# FPGA_POWER.net
KiCad netlist of a schematic drawn in Altium Designer
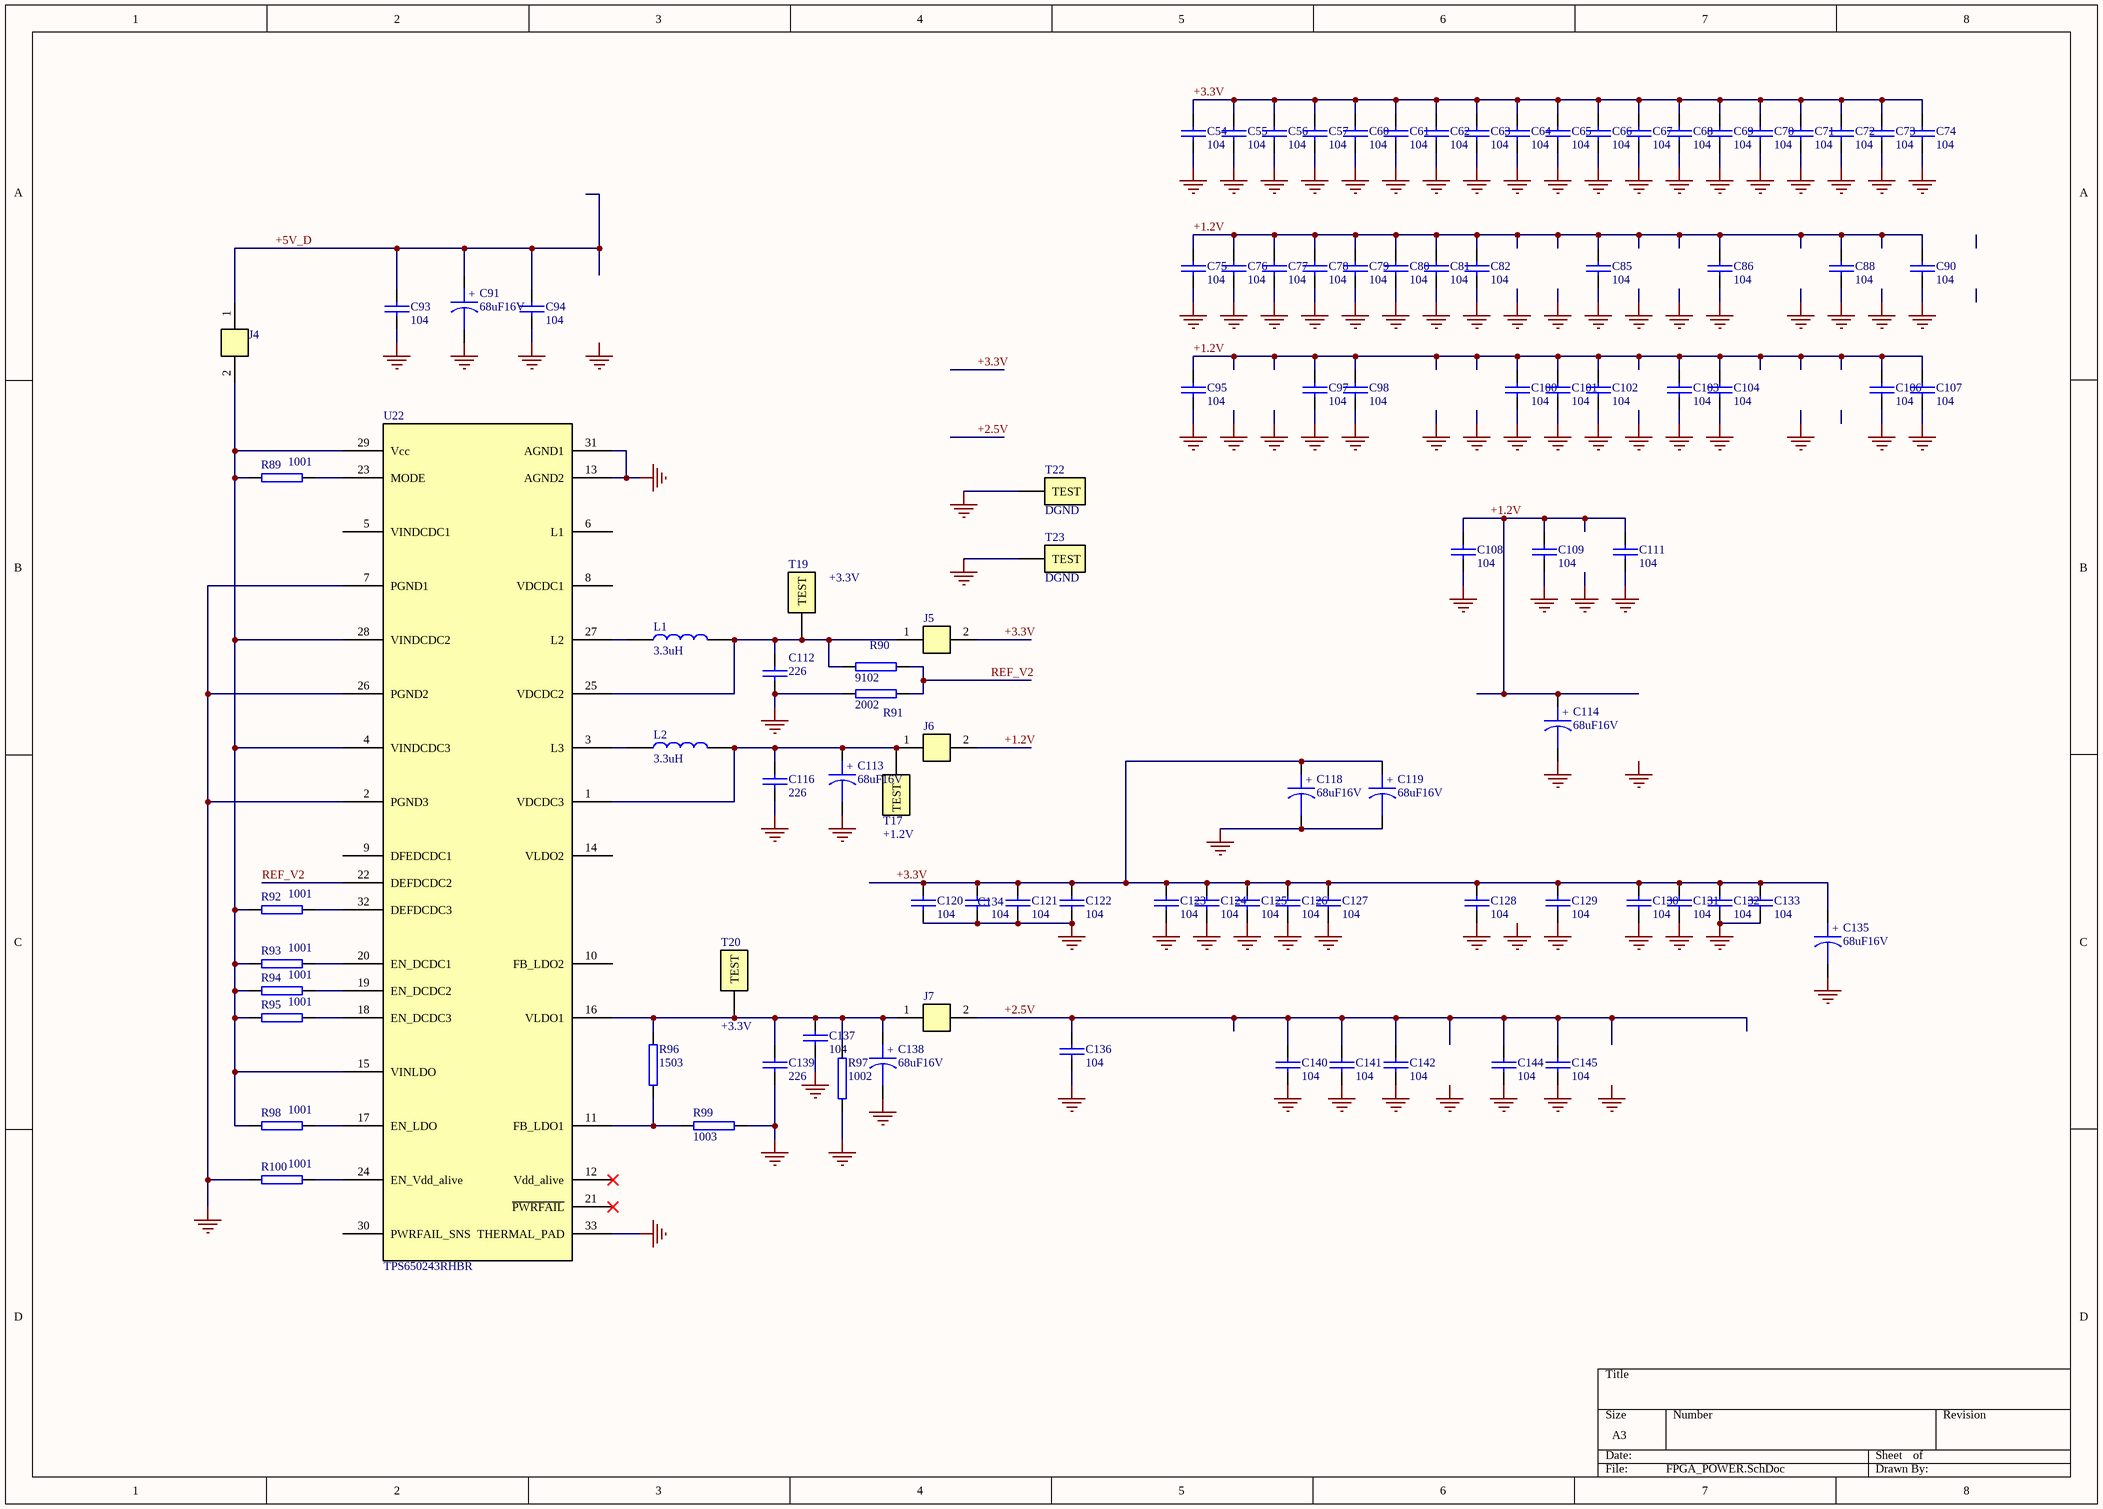
[diagram p0: FPGA_POWER.SchDoc]

(export (version "E")
  (design (tool "Eeschema 10.0.6"))
  (components
    (comp (ref "C54")
      (value "104")
      (footprint "0805C")
      (description "Capacitor")
      (libsource (lib "*") (part "CAP"))
    )
    (comp (ref "C55")
      (value "104")
      (footprint "0402C")
      (description "Capacitor")
      (libsource (lib "*") (part "CAP"))
    )
    (comp (ref "C56")
      (value "104")
      (footprint "0402C")
      (description "Capacitor")
      (libsource (lib "*") (part "CAP"))
    )
    (comp (ref "C57")
      (value "104")
      (footprint "0402C")
      (description "Capacitor")
      (libsource (lib "*") (part "CAP"))
    )
    (comp (ref "C60")
      (value "104")
      (footprint "0402C")
      (description "Capacitor")
      (libsource (lib "*") (part "CAP"))
    )
    (comp (ref "C61")
      (value "104")
      (footprint "0402C")
      (description "Capacitor")
      (libsource (lib "*") (part "CAP"))
    )
    (comp (ref "C62")
      (value "104")
      (footprint "0402C")
      (description "Capacitor")
      (libsource (lib "*") (part "CAP"))
    )
    (comp (ref "C63")
      (value "104")
      (footprint "0402C")
      (description "Capacitor")
      (libsource (lib "*") (part "CAP"))
    )
    (comp (ref "C64")
      (value "104")
      (footprint "0402C")
      (description "Capacitor")
      (libsource (lib "*") (part "CAP"))
    )
    (comp (ref "C65")
      (value "104")
      (footprint "0402C")
      (description "Capacitor")
      (libsource (lib "*") (part "CAP"))
    )
    (comp (ref "C66")
      (value "104")
      (footprint "0402C")
      (description "Capacitor")
      (libsource (lib "*") (part "CAP"))
    )
    (comp (ref "C67")
      (value "104")
      (footprint "0402C")
      (description "Capacitor")
      (libsource (lib "*") (part "CAP"))
    )
    (comp (ref "C68")
      (value "104")
      (footprint "0402C")
      (description "Capacitor")
      (libsource (lib "*") (part "CAP"))
    )
    (comp (ref "C69")
      (value "104")
      (footprint "0402C")
      (description "Capacitor")
      (libsource (lib "*") (part "CAP"))
    )
    (comp (ref "C70")
      (value "104")
      (footprint "0402C")
      (description "Capacitor")
      (libsource (lib "*") (part "CAP"))
    )
    (comp (ref "C71")
      (value "104")
      (footprint "0402C")
      (description "Capacitor")
      (libsource (lib "*") (part "CAP"))
    )
    (comp (ref "C72")
      (value "104")
      (footprint "0402C")
      (description "Capacitor")
      (libsource (lib "*") (part "CAP"))
    )
    (comp (ref "C73")
      (value "104")
      (footprint "0402C")
      (description "Capacitor")
      (libsource (lib "*") (part "CAP"))
    )
    (comp (ref "C74")
      (value "104")
      (footprint "0402C")
      (description "Capacitor")
      (libsource (lib "*") (part "CAP"))
    )
    (comp (ref "C75")
      (value "104")
      (footprint "0805C")
      (description "Capacitor")
      (libsource (lib "*") (part "CAP"))
    )
    (comp (ref "C76")
      (value "104")
      (footprint "0402C")
      (description "Capacitor")
      (libsource (lib "*") (part "CAP"))
    )
    (comp (ref "C77")
      (value "104")
      (footprint "0402C")
      (description "Capacitor")
      (libsource (lib "*") (part "CAP"))
    )
    (comp (ref "C78")
      (value "104")
      (footprint "0805C")
      (description "Capacitor")
      (libsource (lib "*") (part "CAP"))
    )
    (comp (ref "C79")
      (value "104")
      (footprint "0402C")
      (description "Capacitor")
      (libsource (lib "*") (part "CAP"))
    )
    (comp (ref "C80")
      (value "104")
      (footprint "0402C")
      (description "Capacitor")
      (libsource (lib "*") (part "CAP"))
    )
    (comp (ref "C81")
      (value "104")
      (footprint "0402C")
      (description "Capacitor")
      (libsource (lib "*") (part "CAP"))
    )
    (comp (ref "C82")
      (value "104")
      (footprint "0402C")
      (description "Capacitor")
      (libsource (lib "*") (part "CAP"))
    )
    (comp (ref "C85")
      (value "104")
      (footprint "0402C")
      (description "Capacitor")
      (libsource (lib "*") (part "CAP"))
    )
    (comp (ref "C86")
      (value "104")
      (footprint "0402C")
      (description "Capacitor")
      (libsource (lib "*") (part "CAP"))
    )
    (comp (ref "C88")
      (value "104")
      (footprint "0402C")
      (description "Capacitor")
      (libsource (lib "*") (part "CAP"))
    )
    (comp (ref "C90")
      (value "104")
      (footprint "0402C")
      (description "Capacitor")
      (libsource (lib "*") (part "CAP"))
    )
    (comp (ref "C91")
      (value "68uF16V")
      (footprint "6032")
      (description "Capacitor")
      (libsource (lib "*") (part "CAPACITOR POL"))
    )
    (comp (ref "C93")
      (value "104")
      (footprint "0805C")
      (description "Capacitor")
      (libsource (lib "*") (part "CAP"))
    )
    (comp (ref "C94")
      (value "104")
      (footprint "0805C")
      (description "Capacitor")
      (libsource (lib "*") (part "CAP"))
    )
    (comp (ref "C95")
      (value "104")
      (footprint "0402C")
      (description "Capacitor")
      (libsource (lib "*") (part "CAP"))
    )
    (comp (ref "C97")
      (value "104")
      (footprint "0402C")
      (description "Capacitor")
      (libsource (lib "*") (part "CAP"))
    )
    (comp (ref "C98")
      (value "104")
      (footprint "0402C")
      (description "Capacitor")
      (libsource (lib "*") (part "CAP"))
    )
    (comp (ref "C100")
      (value "104")
      (footprint "0402C")
      (description "Capacitor")
      (libsource (lib "*") (part "CAP"))
    )
    (comp (ref "C101")
      (value "104")
      (footprint "0402C")
      (description "Capacitor")
      (libsource (lib "*") (part "CAP"))
    )
    (comp (ref "C102")
      (value "104")
      (footprint "0402C")
      (description "Capacitor")
      (libsource (lib "*") (part "CAP"))
    )
    (comp (ref "C103")
      (value "104")
      (footprint "0402C")
      (description "Capacitor")
      (libsource (lib "*") (part "CAP"))
    )
    (comp (ref "C104")
      (value "104")
      (footprint "0402C")
      (description "Capacitor")
      (libsource (lib "*") (part "CAP"))
    )
    (comp (ref "C106")
      (value "104")
      (footprint "0402C")
      (description "Capacitor")
      (libsource (lib "*") (part "CAP"))
    )
    (comp (ref "C107")
      (value "104")
      (footprint "0402C")
      (description "Capacitor")
      (libsource (lib "*") (part "CAP"))
    )
    (comp (ref "C108")
      (value "104")
      (footprint "0402C")
      (description "Capacitor")
      (libsource (lib "*") (part "CAP"))
    )
    (comp (ref "C109")
      (value "104")
      (footprint "0402C")
      (description "Capacitor")
      (libsource (lib "*") (part "CAP"))
    )
    (comp (ref "C111")
      (value "104")
      (footprint "0402C")
      (description "Capacitor")
      (libsource (lib "*") (part "CAP"))
    )
    (comp (ref "C112")
      (value "226")
      (footprint "C226")
      (description "Capacitor")
      (libsource (lib "*") (part "CAP"))
    )
    (comp (ref "C113")
      (value "68uF16V")
      (footprint "6032")
      (description "Capacitor")
      (libsource (lib "*") (part "CAPACITOR POL"))
    )
    (comp (ref "C114")
      (value "68uF16V")
      (footprint "6032")
      (description "Capacitor")
      (libsource (lib "*") (part "CAPACITOR POL"))
    )
    (comp (ref "C116")
      (value "226")
      (footprint "C226")
      (description "Capacitor")
      (libsource (lib "*") (part "CAP"))
    )
    (comp (ref "C118")
      (value "68uF16V")
      (footprint "6032")
      (description "Capacitor")
      (libsource (lib "*") (part "CAPACITOR POL"))
    )
    (comp (ref "C119")
      (value "68uF16V")
      (footprint "6032")
      (description "Capacitor")
      (libsource (lib "*") (part "CAPACITOR POL"))
    )
    (comp (ref "C120")
      (value "104")
      (footprint "0402C")
      (description "Capacitor")
      (libsource (lib "*") (part "CAP"))
    )
    (comp (ref "C121")
      (value "104")
      (footprint "0402C")
      (description "Capacitor")
      (libsource (lib "*") (part "CAP"))
    )
    (comp (ref "C122")
      (value "104")
      (footprint "0805C")
      (description "Capacitor")
      (libsource (lib "*") (part "CAP"))
    )
    (comp (ref "C123")
      (value "104")
      (footprint "0805C")
      (description "Capacitor")
      (libsource (lib "*") (part "CAP"))
    )
    (comp (ref "C124")
      (value "104")
      (footprint "0805C")
      (description "Capacitor")
      (libsource (lib "*") (part "CAP"))
    )
    (comp (ref "C125")
      (value "104")
      (footprint "0805C")
      (description "Capacitor")
      (libsource (lib "*") (part "CAP"))
    )
    (comp (ref "C126")
      (value "104")
      (footprint "0805C")
      (description "Capacitor")
      (libsource (lib "*") (part "CAP"))
    )
    (comp (ref "C127")
      (value "104")
      (footprint "0402C")
      (description "Capacitor")
      (libsource (lib "*") (part "CAP"))
    )
    (comp (ref "C128")
      (value "104")
      (footprint "0805C")
      (description "Capacitor")
      (libsource (lib "*") (part "CAP"))
    )
    (comp (ref "C129")
      (value "104")
      (footprint "0402C")
      (description "Capacitor")
      (libsource (lib "*") (part "CAP"))
    )
    (comp (ref "C130")
      (value "104")
      (footprint "0402C")
      (description "Capacitor")
      (libsource (lib "*") (part "CAP"))
    )
    (comp (ref "C131")
      (value "104")
      (footprint "0402C")
      (description "Capacitor")
      (libsource (lib "*") (part "CAP"))
    )
    (comp (ref "C132")
      (value "104")
      (footprint "0402C")
      (description "Capacitor")
      (libsource (lib "*") (part "CAP"))
    )
    (comp (ref "C133")
      (value "104")
      (footprint "0402C")
      (description "Capacitor")
      (libsource (lib "*") (part "CAP"))
    )
    (comp (ref "C134")
      (value "104")
      (footprint "0402C")
      (description "Capacitor")
      (libsource (lib "*") (part "CAP"))
    )
    (comp (ref "C135")
      (value "68uF16V")
      (footprint "6032")
      (description "Capacitor")
      (libsource (lib "*") (part "CAPACITOR POL"))
    )
    (comp (ref "C136")
      (value "104")
      (footprint "0805C")
      (description "Capacitor")
      (libsource (lib "*") (part "CAP"))
    )
    (comp (ref "C137")
      (value "104")
      (footprint "0805C")
      (description "Capacitor")
      (libsource (lib "*") (part "CAP"))
    )
    (comp (ref "C138")
      (value "68uF16V")
      (footprint "6032")
      (description "Capacitor")
      (libsource (lib "*") (part "CAPACITOR POL"))
    )
    (comp (ref "C139")
      (value "226")
      (footprint "C226")
      (description "Capacitor")
      (libsource (lib "*") (part "CAP"))
    )
    (comp (ref "C140")
      (value "104")
      (footprint "0402C")
      (description "Capacitor")
      (libsource (lib "*") (part "CAP"))
    )
    (comp (ref "C141")
      (value "104")
      (footprint "0402C")
      (description "Capacitor")
      (libsource (lib "*") (part "CAP"))
    )
    (comp (ref "C142")
      (value "104")
      (footprint "0402C")
      (description "Capacitor")
      (libsource (lib "*") (part "CAP"))
    )
    (comp (ref "C144")
      (value "104")
      (footprint "0805C")
      (description "Capacitor")
      (libsource (lib "*") (part "CAP"))
    )
    (comp (ref "C145")
      (value "104")
      (footprint "0402C")
      (description "Capacitor")
      (libsource (lib "*") (part "CAP"))
    )
    (comp (ref "J4") (value "~") (footprint "I_ON1") (libsource (lib "") (part "I_ON_1")))
    (comp (ref "J5") (value "~") (footprint "I_ON1") (libsource (lib "*") (part "I_ON")))
    (comp (ref "J6") (value "~") (footprint "I_ON1") (libsource (lib "*") (part "I_ON")))
    (comp (ref "J7") (value "~") (footprint "I_ON1") (libsource (lib "*") (part "I_ON")))
    (comp (ref "L1") (value "3.3uH") (footprint "L3R3") (libsource (lib "*") (part "L")))
    (comp (ref "L2") (value "3.3uH") (footprint "L3R3") (libsource (lib "*") (part "L")))
    (comp (ref "R89") (value "1001") (footprint "0603") (libsource (lib "*") (part "RES2")))
    (comp (ref "R90") (value "9102") (footprint "0603") (libsource (lib "*") (part "RES2")))
    (comp (ref "R91") (value "2002") (footprint "0603") (libsource (lib "*") (part "RES2")))
    (comp (ref "R92") (value "1001") (footprint "0603") (libsource (lib "*") (part "RES2")))
    (comp (ref "R93") (value "1001") (footprint "0603") (libsource (lib "*") (part "RES2")))
    (comp (ref "R94") (value "1001") (footprint "0603") (libsource (lib "*") (part "RES2")))
    (comp (ref "R95") (value "1001") (footprint "0603") (libsource (lib "*") (part "RES2")))
    (comp (ref "R96") (value "1503") (footprint "0603") (libsource (lib "*") (part "RES2")))
    (comp (ref "R97") (value "1002") (footprint "0603") (libsource (lib "") (part "RES2_1")))
    (comp (ref "R98") (value "1001") (footprint "0603") (libsource (lib "*") (part "RES2")))
    (comp (ref "R99") (value "1003") (footprint "0603") (libsource (lib "*") (part "RES2")))
    (comp (ref "R100") (value "1001") (footprint "0603") (libsource (lib "*") (part "RES2")))
    (comp (ref "T17") (value "+1.2V") (footprint "TEST") (libsource (lib "") (part "TEST_1")))
    (comp (ref "T19") (value "+3.3V") (footprint "TEST") (libsource (lib "USB30_Project") (part "TEST")))
    (comp (ref "T20") (value "+3.3V") (footprint "TEST") (libsource (lib "USB30_Project") (part "TEST")))
    (comp (ref "T22") (value "DGND") (footprint "TEST") (libsource (lib "") (part "TEST_2")))
    (comp (ref "T23") (value "DGND") (footprint "TEST") (libsource (lib "") (part "TEST_2")))
    (comp (ref "U22") (value "TPS650243RHBR") (footprint "VQFN32-1") (libsource (lib "*") (part "TPS650243")))
  )
  (nets
    (net (code "1") (name "/+1.2V") (class "Default")
      (node (ref "C100") (pin "2") (pinfunction "2_2") (pintype "passive"))
      (node (ref "C101") (pin "2") (pinfunction "2_2") (pintype "passive"))
      (node (ref "C102") (pin "2") (pinfunction "2_2") (pintype "passive"))
      (node (ref "C103") (pin "2") (pinfunction "2_2") (pintype "passive"))
      (node (ref "C104") (pin "2") (pinfunction "2_2") (pintype "passive"))
      (node (ref "C106") (pin "2") (pinfunction "2_2") (pintype "passive"))
      (node (ref "C107") (pin "2") (pinfunction "2_2") (pintype "passive"))
      (node (ref "C108") (pin "2") (pinfunction "2_2") (pintype "passive"))
      (node (ref "C109") (pin "2") (pinfunction "2_2") (pintype "passive"))
      (node (ref "C111") (pin "2") (pinfunction "2_2") (pintype "passive"))
      (node (ref "C114") (pin "1") (pinfunction "1_1") (pintype "passive"))
      (node (ref "C75") (pin "2") (pinfunction "2_2") (pintype "passive"))
      (node (ref "C76") (pin "2") (pinfunction "2_2") (pintype "passive"))
      (node (ref "C77") (pin "2") (pinfunction "2_2") (pintype "passive"))
      (node (ref "C78") (pin "2") (pinfunction "2_2") (pintype "passive"))
      (node (ref "C79") (pin "2") (pinfunction "2_2") (pintype "passive"))
      (node (ref "C80") (pin "2") (pinfunction "2_2") (pintype "passive"))
      (node (ref "C81") (pin "2") (pinfunction "2_2") (pintype "passive"))
      (node (ref "C82") (pin "2") (pinfunction "2_2") (pintype "passive"))
      (node (ref "C85") (pin "2") (pinfunction "2_2") (pintype "passive"))
      (node (ref "C86") (pin "2") (pinfunction "2_2") (pintype "passive"))
      (node (ref "C88") (pin "2") (pinfunction "2_2") (pintype "passive"))
      (node (ref "C90") (pin "2") (pinfunction "2_2") (pintype "passive"))
      (node (ref "C95") (pin "2") (pinfunction "2_2") (pintype "passive"))
      (node (ref "C97") (pin "2") (pinfunction "2_2") (pintype "passive"))
      (node (ref "C98") (pin "2") (pinfunction "2_2") (pintype "passive"))
      (node (ref "J6") (pin "2") (pintype "passive"))
    )
    (net (code "2") (name "/+2.5V") (class "Default")
      (node (ref "C136") (pin "2") (pinfunction "2_2") (pintype "passive"))
      (node (ref "C140") (pin "2") (pinfunction "2_2") (pintype "passive"))
      (node (ref "C141") (pin "2") (pinfunction "2_2") (pintype "passive"))
      (node (ref "C142") (pin "2") (pinfunction "2_2") (pintype "passive"))
      (node (ref "C144") (pin "2") (pinfunction "2_2") (pintype "passive"))
      (node (ref "C145") (pin "2") (pinfunction "2_2") (pintype "passive"))
      (node (ref "J7") (pin "2") (pintype "passive"))
    )
    (net (code "3") (name "/+3.3V") (class "Default")
      (node (ref "C118") (pin "1") (pinfunction "1_1") (pintype "passive"))
      (node (ref "C119") (pin "1") (pinfunction "1_1") (pintype "passive"))
      (node (ref "C120") (pin "2") (pinfunction "2_2") (pintype "passive"))
      (node (ref "C121") (pin "2") (pinfunction "2_2") (pintype "passive"))
      (node (ref "C122") (pin "2") (pinfunction "2_2") (pintype "passive"))
      (node (ref "C123") (pin "2") (pinfunction "2_2") (pintype "passive"))
      (node (ref "C124") (pin "2") (pinfunction "2_2") (pintype "passive"))
      (node (ref "C125") (pin "2") (pinfunction "2_2") (pintype "passive"))
      (node (ref "C126") (pin "2") (pinfunction "2_2") (pintype "passive"))
      (node (ref "C127") (pin "2") (pinfunction "2_2") (pintype "passive"))
      (node (ref "C128") (pin "2") (pinfunction "2_2") (pintype "passive"))
      (node (ref "C129") (pin "2") (pinfunction "2_2") (pintype "passive"))
      (node (ref "C130") (pin "2") (pinfunction "2_2") (pintype "passive"))
      (node (ref "C131") (pin "2") (pinfunction "2_2") (pintype "passive"))
      (node (ref "C132") (pin "2") (pinfunction "2_2") (pintype "passive"))
      (node (ref "C133") (pin "2") (pinfunction "2_2") (pintype "passive"))
      (node (ref "C134") (pin "2") (pinfunction "2_2") (pintype "passive"))
      (node (ref "C135") (pin "1") (pinfunction "1_1") (pintype "passive"))
      (node (ref "C54") (pin "2") (pinfunction "2_2") (pintype "passive"))
      (node (ref "C55") (pin "2") (pinfunction "2_2") (pintype "passive"))
      (node (ref "C56") (pin "2") (pinfunction "2_2") (pintype "passive"))
      (node (ref "C57") (pin "2") (pinfunction "2_2") (pintype "passive"))
      (node (ref "C60") (pin "2") (pinfunction "2_2") (pintype "passive"))
      (node (ref "C61") (pin "2") (pinfunction "2_2") (pintype "passive"))
      (node (ref "C62") (pin "2") (pinfunction "2_2") (pintype "passive"))
      (node (ref "C63") (pin "2") (pinfunction "2_2") (pintype "passive"))
      (node (ref "C64") (pin "2") (pinfunction "2_2") (pintype "passive"))
      (node (ref "C65") (pin "2") (pinfunction "2_2") (pintype "passive"))
      (node (ref "C66") (pin "2") (pinfunction "2_2") (pintype "passive"))
      (node (ref "C67") (pin "2") (pinfunction "2_2") (pintype "passive"))
      (node (ref "C68") (pin "2") (pinfunction "2_2") (pintype "passive"))
      (node (ref "C69") (pin "2") (pinfunction "2_2") (pintype "passive"))
      (node (ref "C70") (pin "2") (pinfunction "2_2") (pintype "passive"))
      (node (ref "C71") (pin "2") (pinfunction "2_2") (pintype "passive"))
      (node (ref "C72") (pin "2") (pinfunction "2_2") (pintype "passive"))
      (node (ref "C73") (pin "2") (pinfunction "2_2") (pintype "passive"))
      (node (ref "C74") (pin "2") (pinfunction "2_2") (pintype "passive"))
      (node (ref "J5") (pin "2") (pintype "passive"))
    )
    (net (code "4") (name "/+5V_D") (class "Default")
      (node (ref "C91") (pin "1") (pinfunction "1_1") (pintype "passive"))
      (node (ref "C93") (pin "2") (pinfunction "2_2") (pintype "passive"))
      (node (ref "C94") (pin "2") (pinfunction "2_2") (pintype "passive"))
      (node (ref "J4") (pin "1") (pintype "passive"))
    )
    (net (code "5") (name "/REF_V2") (class "Default")
      (node (ref "R90") (pin "2") (pinfunction "2_2") (pintype "passive"))
      (node (ref "R91") (pin "1") (pinfunction "1_1") (pintype "passive"))
      (node (ref "U22") (pin "22") (pinfunction "DEFDCDC2_22") (pintype "passive"))
    )
    (net (code "6") (name "DGND") (class "Default")
      (node (ref "C100") (pin "1") (pinfunction "1_1") (pintype "passive"))
      (node (ref "C101") (pin "1") (pinfunction "1_1") (pintype "passive"))
      (node (ref "C102") (pin "1") (pinfunction "1_1") (pintype "passive"))
      (node (ref "C103") (pin "1") (pinfunction "1_1") (pintype "passive"))
      (node (ref "C104") (pin "1") (pinfunction "1_1") (pintype "passive"))
      (node (ref "C106") (pin "1") (pinfunction "1_1") (pintype "passive"))
      (node (ref "C107") (pin "1") (pinfunction "1_1") (pintype "passive"))
      (node (ref "C108") (pin "1") (pinfunction "1_1") (pintype "passive"))
      (node (ref "C109") (pin "1") (pinfunction "1_1") (pintype "passive"))
      (node (ref "C111") (pin "1") (pinfunction "1_1") (pintype "passive"))
      (node (ref "C112") (pin "2") (pinfunction "2_2") (pintype "passive"))
      (node (ref "C113") (pin "2") (pinfunction "2_2") (pintype "passive"))
      (node (ref "C114") (pin "2") (pinfunction "2_2") (pintype "passive"))
      (node (ref "C116") (pin "2") (pinfunction "2_2") (pintype "passive"))
      (node (ref "C118") (pin "2") (pinfunction "2_2") (pintype "passive"))
      (node (ref "C119") (pin "2") (pinfunction "2_2") (pintype "passive"))
      (node (ref "C120") (pin "1") (pinfunction "1_1") (pintype "passive"))
      (node (ref "C121") (pin "1") (pinfunction "1_1") (pintype "passive"))
      (node (ref "C122") (pin "1") (pinfunction "1_1") (pintype "passive"))
      (node (ref "C123") (pin "1") (pinfunction "1_1") (pintype "passive"))
      (node (ref "C124") (pin "1") (pinfunction "1_1") (pintype "passive"))
      (node (ref "C125") (pin "1") (pinfunction "1_1") (pintype "passive"))
      (node (ref "C126") (pin "1") (pinfunction "1_1") (pintype "passive"))
      (node (ref "C127") (pin "1") (pinfunction "1_1") (pintype "passive"))
      (node (ref "C128") (pin "1") (pinfunction "1_1") (pintype "passive"))
      (node (ref "C129") (pin "1") (pinfunction "1_1") (pintype "passive"))
      (node (ref "C130") (pin "1") (pinfunction "1_1") (pintype "passive"))
      (node (ref "C131") (pin "1") (pinfunction "1_1") (pintype "passive"))
      (node (ref "C132") (pin "1") (pinfunction "1_1") (pintype "passive"))
      (node (ref "C133") (pin "1") (pinfunction "1_1") (pintype "passive"))
      (node (ref "C134") (pin "1") (pinfunction "1_1") (pintype "passive"))
      (node (ref "C135") (pin "2") (pinfunction "2_2") (pintype "passive"))
      (node (ref "C136") (pin "1") (pinfunction "1_1") (pintype "passive"))
      (node (ref "C137") (pin "1") (pinfunction "1_1") (pintype "passive"))
      (node (ref "C138") (pin "2") (pinfunction "2_2") (pintype "passive"))
      (node (ref "C139") (pin "2") (pinfunction "2_2") (pintype "passive"))
      (node (ref "C140") (pin "1") (pinfunction "1_1") (pintype "passive"))
      (node (ref "C141") (pin "1") (pinfunction "1_1") (pintype "passive"))
      (node (ref "C142") (pin "1") (pinfunction "1_1") (pintype "passive"))
      (node (ref "C144") (pin "1") (pinfunction "1_1") (pintype "passive"))
      (node (ref "C145") (pin "1") (pinfunction "1_1") (pintype "passive"))
      (node (ref "C54") (pin "1") (pinfunction "1_1") (pintype "passive"))
      (node (ref "C55") (pin "1") (pinfunction "1_1") (pintype "passive"))
      (node (ref "C56") (pin "1") (pinfunction "1_1") (pintype "passive"))
      (node (ref "C57") (pin "1") (pinfunction "1_1") (pintype "passive"))
      (node (ref "C60") (pin "1") (pinfunction "1_1") (pintype "passive"))
      (node (ref "C61") (pin "1") (pinfunction "1_1") (pintype "passive"))
      (node (ref "C62") (pin "1") (pinfunction "1_1") (pintype "passive"))
      (node (ref "C63") (pin "1") (pinfunction "1_1") (pintype "passive"))
      (node (ref "C64") (pin "1") (pinfunction "1_1") (pintype "passive"))
      (node (ref "C65") (pin "1") (pinfunction "1_1") (pintype "passive"))
      (node (ref "C66") (pin "1") (pinfunction "1_1") (pintype "passive"))
      (node (ref "C67") (pin "1") (pinfunction "1_1") (pintype "passive"))
      (node (ref "C68") (pin "1") (pinfunction "1_1") (pintype "passive"))
      (node (ref "C69") (pin "1") (pinfunction "1_1") (pintype "passive"))
      (node (ref "C70") (pin "1") (pinfunction "1_1") (pintype "passive"))
      (node (ref "C71") (pin "1") (pinfunction "1_1") (pintype "passive"))
      (node (ref "C72") (pin "1") (pinfunction "1_1") (pintype "passive"))
      (node (ref "C73") (pin "1") (pinfunction "1_1") (pintype "passive"))
      (node (ref "C74") (pin "1") (pinfunction "1_1") (pintype "passive"))
      (node (ref "C75") (pin "1") (pinfunction "1_1") (pintype "passive"))
      (node (ref "C76") (pin "1") (pinfunction "1_1") (pintype "passive"))
      (node (ref "C77") (pin "1") (pinfunction "1_1") (pintype "passive"))
      (node (ref "C78") (pin "1") (pinfunction "1_1") (pintype "passive"))
      (node (ref "C79") (pin "1") (pinfunction "1_1") (pintype "passive"))
      (node (ref "C80") (pin "1") (pinfunction "1_1") (pintype "passive"))
      (node (ref "C81") (pin "1") (pinfunction "1_1") (pintype "passive"))
      (node (ref "C82") (pin "1") (pinfunction "1_1") (pintype "passive"))
      (node (ref "C85") (pin "1") (pinfunction "1_1") (pintype "passive"))
      (node (ref "C86") (pin "1") (pinfunction "1_1") (pintype "passive"))
      (node (ref "C88") (pin "1") (pinfunction "1_1") (pintype "passive"))
      (node (ref "C90") (pin "1") (pinfunction "1_1") (pintype "passive"))
      (node (ref "C91") (pin "2") (pinfunction "2_2") (pintype "passive"))
      (node (ref "C93") (pin "1") (pinfunction "1_1") (pintype "passive"))
      (node (ref "C94") (pin "1") (pinfunction "1_1") (pintype "passive"))
      (node (ref "C95") (pin "1") (pinfunction "1_1") (pintype "passive"))
      (node (ref "C97") (pin "1") (pinfunction "1_1") (pintype "passive"))
      (node (ref "C98") (pin "1") (pinfunction "1_1") (pintype "passive"))
      (node (ref "R100") (pin "1") (pinfunction "1_1") (pintype "passive"))
      (node (ref "R91") (pin "2") (pinfunction "2_2") (pintype "passive"))
      (node (ref "R97") (pin "2") (pinfunction "2_2") (pintype "passive"))
      (node (ref "R99") (pin "2") (pinfunction "2_2") (pintype "passive"))
      (node (ref "T22") (pin "1") (pinfunction "TEST_1") (pintype "passive"))
      (node (ref "T23") (pin "1") (pinfunction "TEST_1") (pintype "passive"))
      (node (ref "U22") (pin "13") (pinfunction "AGND2_13") (pintype "passive"))
      (node (ref "U22") (pin "2") (pinfunction "PGND3_2") (pintype "passive"))
      (node (ref "U22") (pin "26") (pinfunction "PGND2_26") (pintype "passive"))
      (node (ref "U22") (pin "31") (pinfunction "AGND1_31") (pintype "passive"))
      (node (ref "U22") (pin "33") (pinfunction "THERMAL_PAD_33") (pintype "passive"))
      (node (ref "U22") (pin "7") (pinfunction "PGND1_7") (pintype "passive"))
    )
    (net (code "7") (name "Net-(T17-TEST)") (class "Default")
      (node (ref "C113") (pin "1") (pinfunction "1_1") (pintype "passive"))
      (node (ref "C116") (pin "1") (pinfunction "1_1") (pintype "passive"))
      (node (ref "J6") (pin "1") (pintype "passive"))
      (node (ref "L2") (pin "2") (pinfunction "2_2") (pintype "passive"))
      (node (ref "T17") (pin "1") (pinfunction "TEST_1") (pintype "passive"))
      (node (ref "U22") (pin "1") (pinfunction "VDCDC3_1") (pintype "passive"))
    )
    (net (code "8") (name "Net-(T19-TEST)") (class "Default")
      (node (ref "C112") (pin "1") (pinfunction "1_1") (pintype "passive"))
      (node (ref "J5") (pin "1") (pintype "passive"))
      (node (ref "L1") (pin "2") (pinfunction "2_2") (pintype "passive"))
      (node (ref "R90") (pin "1") (pinfunction "1_1") (pintype "passive"))
      (node (ref "T19") (pin "1") (pinfunction "TEST_1") (pintype "passive"))
      (node (ref "U22") (pin "25") (pinfunction "VDCDC2_25") (pintype "passive"))
    )
    (net (code "9") (name "Net-(T20-TEST)") (class "Default")
      (node (ref "C137") (pin "2") (pinfunction "2_2") (pintype "passive"))
      (node (ref "C138") (pin "1") (pinfunction "1_1") (pintype "passive"))
      (node (ref "C139") (pin "1") (pinfunction "1_1") (pintype "passive"))
      (node (ref "J7") (pin "1") (pintype "passive"))
      (node (ref "R96") (pin "2") (pinfunction "2_2") (pintype "passive"))
      (node (ref "R97") (pin "1") (pinfunction "1_1") (pintype "passive"))
      (node (ref "T20") (pin "1") (pinfunction "TEST_1") (pintype "passive"))
      (node (ref "U22") (pin "16") (pinfunction "VLDO1_16") (pintype "passive"))
    )
    (net (code "10") (name "Net-(U22-DEFDCDC3)") (class "Default")
      (node (ref "R92") (pin "2") (pinfunction "2_2") (pintype "passive"))
      (node (ref "U22") (pin "32") (pinfunction "DEFDCDC3_32") (pintype "passive"))
    )
    (net (code "11") (name "Net-(U22-EN_DCDC1)") (class "Default")
      (node (ref "R93") (pin "2") (pinfunction "2_2") (pintype "passive"))
      (node (ref "U22") (pin "20") (pinfunction "EN_DCDC1_20") (pintype "passive"))
    )
    (net (code "12") (name "Net-(U22-EN_DCDC2)") (class "Default")
      (node (ref "R94") (pin "2") (pinfunction "2_2") (pintype "passive"))
      (node (ref "U22") (pin "19") (pinfunction "EN_DCDC2_19") (pintype "passive"))
    )
    (net (code "13") (name "Net-(U22-EN_DCDC3)") (class "Default")
      (node (ref "R95") (pin "2") (pinfunction "2_2") (pintype "passive"))
      (node (ref "U22") (pin "18") (pinfunction "EN_DCDC3_18") (pintype "passive"))
    )
    (net (code "14") (name "Net-(U22-EN_LDO)") (class "Default")
      (node (ref "R98") (pin "2") (pinfunction "2_2") (pintype "passive"))
      (node (ref "U22") (pin "17") (pinfunction "EN_LDO_17") (pintype "passive"))
    )
    (net (code "15") (name "Net-(U22-EN_Vdd_alive)") (class "Default")
      (node (ref "R100") (pin "2") (pinfunction "2_2") (pintype "passive"))
      (node (ref "U22") (pin "24") (pinfunction "EN_Vdd_alive_24") (pintype "passive"))
    )
    (net (code "16") (name "Net-(U22-FB_LDO1)") (class "Default")
      (node (ref "R96") (pin "1") (pinfunction "1_1") (pintype "passive"))
      (node (ref "R99") (pin "1") (pinfunction "1_1") (pintype "passive"))
      (node (ref "U22") (pin "11") (pinfunction "FB_LDO1_11") (pintype "passive"))
    )
    (net (code "17") (name "Net-(U22-L2)") (class "Default")
      (node (ref "L1") (pin "1") (pinfunction "1_1") (pintype "passive"))
      (node (ref "U22") (pin "27") (pinfunction "L2_27") (pintype "passive"))
    )
    (net (code "18") (name "Net-(U22-L3)") (class "Default")
      (node (ref "L2") (pin "1") (pinfunction "1_1") (pintype "passive"))
      (node (ref "U22") (pin "3") (pinfunction "L3_3") (pintype "passive"))
    )
    (net (code "19") (name "Net-(U22-MODE)") (class "Default")
      (node (ref "R89") (pin "2") (pinfunction "2_2") (pintype "passive"))
      (node (ref "U22") (pin "23") (pinfunction "MODE_23") (pintype "passive"))
    )
    (net (code "20") (name "Net-(U22-VINDCDC2)") (class "Default")
      (node (ref "J4") (pin "2") (pintype "passive"))
      (node (ref "R89") (pin "1") (pinfunction "1_1") (pintype "passive"))
      (node (ref "R92") (pin "1") (pinfunction "1_1") (pintype "passive"))
      (node (ref "R93") (pin "1") (pinfunction "1_1") (pintype "passive"))
      (node (ref "R94") (pin "1") (pinfunction "1_1") (pintype "passive"))
      (node (ref "R95") (pin "1") (pinfunction "1_1") (pintype "passive"))
      (node (ref "R98") (pin "1") (pinfunction "1_1") (pintype "passive"))
      (node (ref "U22") (pin "15") (pinfunction "VINLDO_15") (pintype "passive"))
      (node (ref "U22") (pin "28") (pinfunction "VINDCDC2_28") (pintype "passive"))
      (node (ref "U22") (pin "29") (pinfunction "Vcc_29") (pintype "passive"))
      (node (ref "U22") (pin "4") (pinfunction "VINDCDC3_4") (pintype "passive"))
    )
    (net (code "21") (name "unconnected-(U22-DFEDCDC1-Pad9)") (class "Default")
      (node (ref "U22") (pin "9") (pinfunction "DFEDCDC1_9") (pintype "passive"))
    )
    (net (code "22") (name "unconnected-(U22-FB_LDO2-Pad10)") (class "Default")
      (node (ref "U22") (pin "10") (pinfunction "FB_LDO2_10") (pintype "passive"))
    )
    (net (code "23") (name "unconnected-(U22-L1-Pad6)") (class "Default")
      (node (ref "U22") (pin "6") (pinfunction "L1_6") (pintype "passive"))
    )
    (net (code "24") (name "unconnected-(U22-PWRFAIL_SNS-Pad30)") (class "Default")
      (node (ref "U22") (pin "30") (pinfunction "PWRFAIL_SNS_30") (pintype "passive"))
    )
    (net (code "25") (name "unconnected-(U22-VDCDC1-Pad8)") (class "Default")
      (node (ref "U22") (pin "8") (pinfunction "VDCDC1_8") (pintype "passive"))
    )
    (net (code "26") (name "unconnected-(U22-VINDCDC1-Pad5)") (class "Default")
      (node (ref "U22") (pin "5") (pinfunction "VINDCDC1_5") (pintype "passive"))
    )
    (net (code "27") (name "unconnected-(U22-VLDO2-Pad14)") (class "Default")
      (node (ref "U22") (pin "14") (pinfunction "VLDO2_14") (pintype "passive"))
    )
    (net (code "28") (name "unconnected-(U22-Vdd_alive-Pad12)") (class "Default")
      (node (ref "U22") (pin "12") (pinfunction "Vdd_alive_12") (pintype "passive+no_connect"))
    )
    (net (code "29") (name "unconnected-(U22-~{PWRFAIL}-Pad21)") (class "Default")
      (node (ref "U22") (pin "21") (pinfunction "~{PWRFAIL}_21") (pintype "passive+no_connect"))
    )
  )
)
